# mailboxWiFi.net
KiCad netlist of a schematic drawn in EAGLE
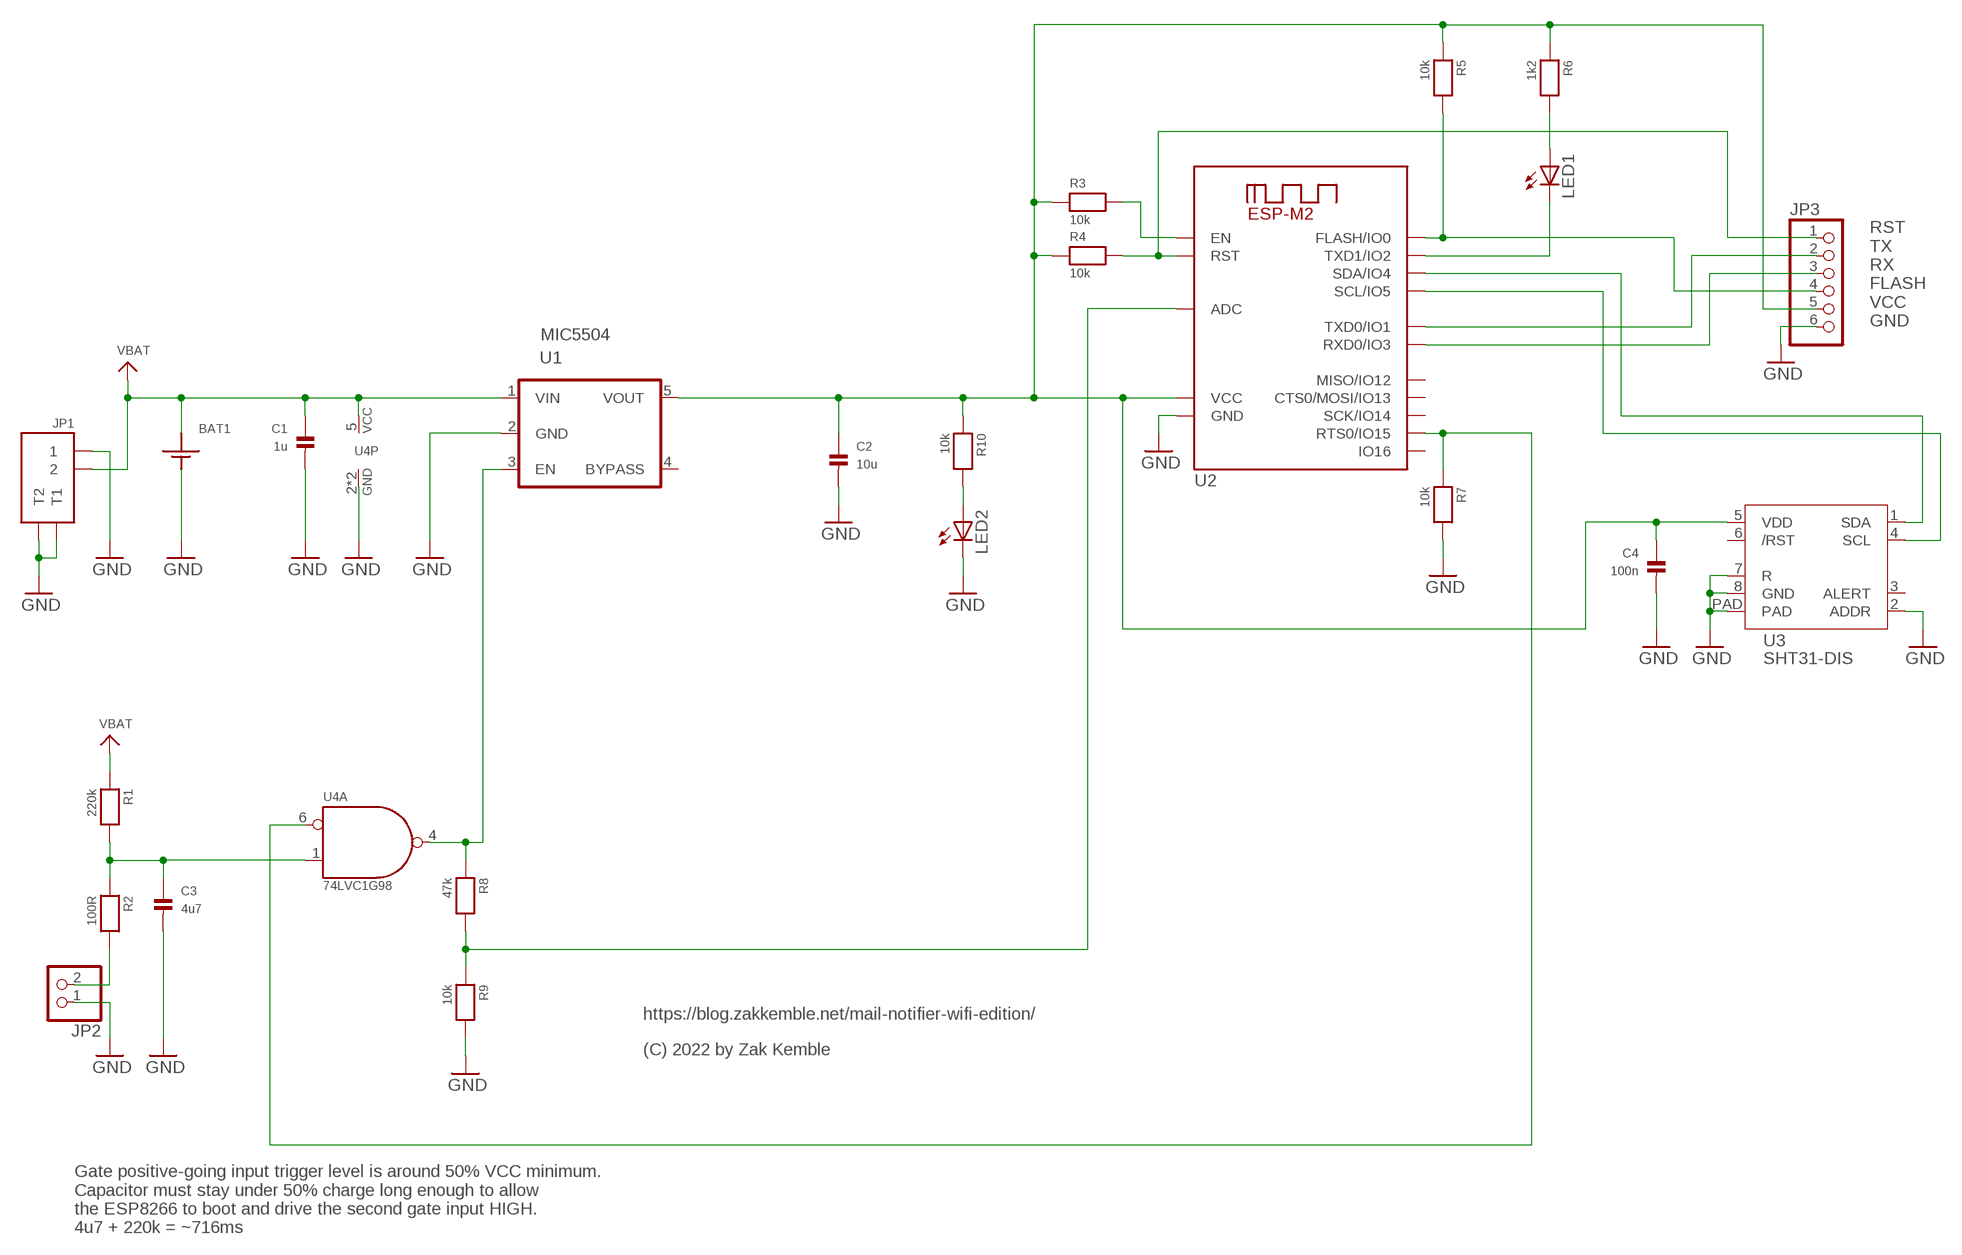
[diagram p0: schematic, sheet 1]

(export (version "E")
  (design (tool "Eeschema 10.0.6"))
  (components
    (comp (ref "BAT1")
      (value "BATTERY_HOLDER1XAAA_PCB")
      (footprint "eagle-import:BATT_HOLDER_AAA_PCB")
      (libsource (lib "eagle-import") (part "BATTERY_HOLDER1XAAA_PCB"))
    )
    (comp (ref "C1")
      (value "1u")
      (footprint "eagle-import:0805_NO_OUTLINE")
      (libsource (lib "eagle-import") (part "CAP_CERAMIC0805"))
    )
    (comp (ref "C2")
      (value "10u")
      (footprint "eagle-import:1206")
      (libsource (lib "eagle-import") (part "CAP_CERAMIC1206"))
    )
    (comp (ref "C3")
      (value "4u7")
      (footprint "eagle-import:0805_NO_OUTLINE")
      (libsource (lib "eagle-import") (part "CAP_CERAMIC0805"))
    )
    (comp (ref "C4")
      (value "100n")
      (footprint "eagle-import:0402_XSMALL")
      (libsource (lib "eagle-import") (part "CAP_CERAMIC0402_XSMALL"))
    )
    (comp (ref "JP1")
      (value "2WAY-SMDVERT")
      (footprint "eagle-import:2WAY-SMD")
      (libsource (lib "eagle-import") (part "2WAY-SMDVERT"))
    )
    (comp (ref "JP2")
      (value "PINHD-1X2/90")
      (footprint "eagle-import:1X02_90")
      (libsource (lib "eagle-import") (part "PINHD-1X2/90"))
    )
    (comp (ref "JP3")
      (value "PINHD-1X6")
      (footprint "eagle-import:1X06")
      (libsource (lib "eagle-import") (part "PINHD-1X6"))
    )
    (comp (ref "LED1")
      (value "LED0402_XSMALL")
      (footprint "eagle-import:0402_DIODE_XSMALL")
      (libsource (lib "eagle-import") (part "LED0402_XSMALL"))
    )
    (comp (ref "LED2")
      (value "LED0402_XSMALL")
      (footprint "eagle-import:0402_DIODE_XSMALL")
      (libsource (lib "eagle-import") (part "LED0402_XSMALL"))
    )
    (comp (ref "R1")
      (value "220k")
      (footprint "eagle-import:0402_XSMALL")
      (libsource (lib "eagle-import") (part "RESISTOR0402_XSMALL"))
    )
    (comp (ref "R2")
      (value "100R")
      (footprint "eagle-import:0402_XSMALL")
      (libsource (lib "eagle-import") (part "RESISTOR0402_XSMALL"))
    )
    (comp (ref "R3")
      (value "10k")
      (footprint "eagle-import:0402_XSMALL")
      (libsource (lib "eagle-import") (part "RESISTOR0402_XSMALL"))
    )
    (comp (ref "R4")
      (value "10k")
      (footprint "eagle-import:0402_XSMALL")
      (libsource (lib "eagle-import") (part "RESISTOR0402_XSMALL"))
    )
    (comp (ref "R5")
      (value "10k")
      (footprint "eagle-import:0402_XSMALL")
      (libsource (lib "eagle-import") (part "RESISTOR0402_XSMALL"))
    )
    (comp (ref "R6")
      (value "1k2")
      (footprint "eagle-import:0402_XSMALL")
      (libsource (lib "eagle-import") (part "RESISTOR0402_XSMALL"))
    )
    (comp (ref "R7")
      (value "10k")
      (footprint "eagle-import:0402_XSMALL")
      (libsource (lib "eagle-import") (part "RESISTOR0402_XSMALL"))
    )
    (comp (ref "R8")
      (value "47k")
      (footprint "eagle-import:0402_XSMALL")
      (libsource (lib "eagle-import") (part "RESISTOR0402_XSMALL"))
    )
    (comp (ref "R9")
      (value "10k")
      (footprint "eagle-import:0402_XSMALL")
      (libsource (lib "eagle-import") (part "RESISTOR0402_XSMALL"))
    )
    (comp (ref "R10")
      (value "10k")
      (footprint "eagle-import:0402_XSMALL")
      (libsource (lib "eagle-import") (part "RESISTOR0402_XSMALL"))
    )
    (comp (ref "U1")
      (value "MIC5504")
      (footprint "eagle-import:SOT23-5_SM_PAD")
      (libsource (lib "eagle-import") (part "REGULATOR_5SOT23-5"))
    )
    (comp (ref "U2")
      (value "ESP-M2")
      (footprint "eagle-import:ESP-M2")
      (libsource (lib "eagle-import") (part "ESP-M2"))
    )
    (comp (ref "U3")
      (value "SHT31-DIS")
      (footprint "eagle-import:DFN_2.5X2.5_8")
      (libsource (lib "eagle-import") (part "SHT3X-DIS"))
    )
    (comp (ref "U4")
      (value "74LVC1G98")
      (footprint "eagle-import:SOT-363")
      (libsource (lib "eagle-import") (part "74LVC1G98-NAND_1INVSOT-363"))
    )
  )
  (nets
    (net (code "1") (name "GND") (class "Default")
      (node (ref "BAT1") (pin "NEG") (pinfunction "NEG_NEG") (pintype "passive"))
      (node (ref "C1") (pin "2") (pinfunction "P$2_2") (pintype "passive"))
      (node (ref "C2") (pin "2") (pinfunction "P$2_2") (pintype "passive"))
      (node (ref "C3") (pin "2") (pinfunction "P$2_2") (pintype "passive"))
      (node (ref "C4") (pin "2") (pinfunction "P$2_2") (pintype "passive"))
      (node (ref "JP1") (pin "1") (pinfunction "1_1") (pintype "passive"))
      (node (ref "JP1") (pin "TAB$1") (pinfunction "T1_TAB$1") (pintype "passive"))
      (node (ref "JP1") (pin "TAB$2") (pinfunction "T2_TAB$2") (pintype "passive"))
      (node (ref "JP2") (pin "1") (pinfunction "1_1") (pintype "passive"))
      (node (ref "JP3") (pin "6") (pinfunction "6_6") (pintype "passive"))
      (node (ref "LED2") (pin "2") (pinfunction "C_2") (pintype "passive"))
      (node (ref "R7") (pin "2") (pinfunction "2_2") (pintype "passive"))
      (node (ref "R9") (pin "2") (pinfunction "2_2") (pintype "passive"))
      (node (ref "U1") (pin "2") (pinfunction "GND_2") (pintype "passive"))
      (node (ref "U2") (pin "8") (pinfunction "GND_8") (pintype "bidirectional"))
      (node (ref "U3") (pin "2") (pinfunction "ADDR_2") (pintype "bidirectional"))
      (node (ref "U3") (pin "7") (pinfunction "R_7") (pintype "bidirectional"))
      (node (ref "U3") (pin "8") (pinfunction "GND_8") (pintype "bidirectional"))
      (node (ref "U3") (pin "PAD") (pinfunction "PAD_PAD") (pintype "bidirectional"))
      (node (ref "U4") (pin "2") (pinfunction "GND_2") (pintype "power_in"))
      (node (ref "U4") (pin "3") (pinfunction "GND_3") (pintype "power_in"))
    )
    (net (code "2") (name "Net-(C2-P$1)") (class "Default")
      (node (ref "C2") (pin "1") (pinfunction "P$1_1") (pintype "passive"))
      (node (ref "C4") (pin "1") (pinfunction "P$1_1") (pintype "passive"))
      (node (ref "JP3") (pin "5") (pinfunction "5_5") (pintype "passive"))
      (node (ref "R10") (pin "1") (pinfunction "1_1") (pintype "passive"))
      (node (ref "R3") (pin "1") (pinfunction "1_1") (pintype "passive"))
      (node (ref "R4") (pin "1") (pinfunction "1_1") (pintype "passive"))
      (node (ref "R5") (pin "1") (pinfunction "1_1") (pintype "passive"))
      (node (ref "R6") (pin "1") (pinfunction "1_1") (pintype "passive"))
      (node (ref "U1") (pin "5") (pinfunction "VOUT_5") (pintype "output"))
      (node (ref "U2") (pin "7") (pinfunction "VCC_7") (pintype "bidirectional"))
      (node (ref "U3") (pin "5") (pinfunction "VDD_5") (pintype "bidirectional"))
    )
    (net (code "3") (name "Net-(C3-P$1)") (class "Default")
      (node (ref "C3") (pin "1") (pinfunction "P$1_1") (pintype "passive"))
      (node (ref "R1") (pin "2") (pinfunction "2_2") (pintype "passive"))
      (node (ref "R2") (pin "1") (pinfunction "1_1") (pintype "passive"))
      (node (ref "U4") (pin "1") (pinfunction "B_1") (pintype "input"))
    )
    (net (code "4") (name "Net-(JP2-Pad2)") (class "Default")
      (node (ref "JP2") (pin "2") (pinfunction "2_2") (pintype "passive"))
      (node (ref "R2") (pin "2") (pinfunction "2_2") (pintype "passive"))
    )
    (net (code "5") (name "Net-(LED1-A)") (class "Default")
      (node (ref "LED1") (pin "1") (pinfunction "A_1") (pintype "passive"))
      (node (ref "R6") (pin "2") (pinfunction "2_2") (pintype "passive"))
    )
    (net (code "6") (name "Net-(LED1-C)") (class "Default")
      (node (ref "LED1") (pin "2") (pinfunction "C_2") (pintype "passive"))
      (node (ref "U2") (pin "9") (pinfunction "TXD1/IO2_9") (pintype "bidirectional"))
    )
    (net (code "7") (name "Net-(LED2-A)") (class "Default")
      (node (ref "LED2") (pin "1") (pinfunction "A_1") (pintype "passive"))
      (node (ref "R10") (pin "2") (pinfunction "2_2") (pintype "passive"))
    )
    (net (code "8") (name "Net-(U1-EN)") (class "Default")
      (node (ref "R8") (pin "1") (pinfunction "1_1") (pintype "passive"))
      (node (ref "U1") (pin "3") (pinfunction "EN_3") (pintype "input"))
      (node (ref "U4") (pin "4") (pinfunction "Y_4") (pintype "output"))
    )
    (net (code "9") (name "Net-(U2-ADC)") (class "Default")
      (node (ref "R8") (pin "2") (pinfunction "2_2") (pintype "passive"))
      (node (ref "R9") (pin "1") (pinfunction "1_1") (pintype "passive"))
      (node (ref "U2") (pin "1") (pinfunction "ADC_1") (pintype "bidirectional"))
    )
    (net (code "10") (name "Net-(U2-EN)") (class "Default")
      (node (ref "R3") (pin "2") (pinfunction "2_2") (pintype "passive"))
      (node (ref "U2") (pin "2") (pinfunction "EN_2") (pintype "bidirectional"))
    )
    (net (code "11") (name "Net-(U2-FLASH{slash}IO0)") (class "Default")
      (node (ref "JP3") (pin "4") (pinfunction "4_4") (pintype "passive"))
      (node (ref "R5") (pin "2") (pinfunction "2_2") (pintype "passive"))
      (node (ref "U2") (pin "10") (pinfunction "FLASH/IO0_10") (pintype "bidirectional"))
    )
    (net (code "12") (name "Net-(U2-RST)") (class "Default")
      (node (ref "JP3") (pin "1") (pinfunction "1_1") (pintype "passive"))
      (node (ref "R4") (pin "2") (pinfunction "2_2") (pintype "passive"))
      (node (ref "U2") (pin "15") (pinfunction "RST_15") (pintype "bidirectional"))
    )
    (net (code "13") (name "Net-(U2-RTS0{slash}IO15)") (class "Default")
      (node (ref "R7") (pin "1") (pinfunction "1_1") (pintype "passive"))
      (node (ref "U2") (pin "6") (pinfunction "RTS0/IO15_6") (pintype "bidirectional"))
      (node (ref "U4") (pin "6") (pinfunction "A_6") (pintype "input"))
    )
    (net (code "14") (name "Net-(U2-RXD0{slash}IO3)") (class "Default")
      (node (ref "JP3") (pin "3") (pinfunction "3_3") (pintype "passive"))
      (node (ref "U2") (pin "13") (pinfunction "RXD0/IO3_13") (pintype "bidirectional"))
    )
    (net (code "15") (name "Net-(U2-SCL{slash}IO5)") (class "Default")
      (node (ref "U2") (pin "12") (pinfunction "SCL/IO5_12") (pintype "bidirectional"))
      (node (ref "U3") (pin "4") (pinfunction "SCL_4") (pintype "bidirectional"))
    )
    (net (code "16") (name "Net-(U2-SDA{slash}IO4)") (class "Default")
      (node (ref "U2") (pin "11") (pinfunction "SDA/IO4_11") (pintype "bidirectional"))
      (node (ref "U3") (pin "1") (pinfunction "SDA_1") (pintype "bidirectional"))
    )
    (net (code "17") (name "Net-(U2-TXD0{slash}IO1)") (class "Default")
      (node (ref "JP3") (pin "2") (pinfunction "2_2") (pintype "passive"))
      (node (ref "U2") (pin "14") (pinfunction "TXD0/IO1_14") (pintype "bidirectional"))
    )
    (net (code "18") (name "VBAT") (class "Default")
      (node (ref "BAT1") (pin "POS") (pinfunction "POS_POS") (pintype "power_in"))
      (node (ref "C1") (pin "1") (pinfunction "P$1_1") (pintype "passive"))
      (node (ref "JP1") (pin "2") (pinfunction "2_2") (pintype "passive"))
      (node (ref "R1") (pin "1") (pinfunction "1_1") (pintype "passive"))
      (node (ref "U1") (pin "1") (pinfunction "VIN_1") (pintype "power_in"))
      (node (ref "U4") (pin "5") (pinfunction "VCC_5") (pintype "power_in"))
    )
    (net (code "19") (name "unconnected-(U1-BYPASS-Pad4)") (class "Default")
      (node (ref "U1") (pin "4") (pinfunction "BYPASS_4") (pintype "passive"))
    )
    (net (code "20") (name "unconnected-(U2-CTS0{slash}MOSI{slash}IO13-Pad5)") (class "Default")
      (node (ref "U2") (pin "5") (pinfunction "CTS0/MOSI/IO13_5") (pintype "bidirectional"))
    )
    (net (code "21") (name "unconnected-(U2-IO16-Pad16)") (class "Default")
      (node (ref "U2") (pin "16") (pinfunction "IO16_16") (pintype "bidirectional"))
    )
    (net (code "22") (name "unconnected-(U2-MISO{slash}IO12-Pad4)") (class "Default")
      (node (ref "U2") (pin "4") (pinfunction "MISO/IO12_4") (pintype "bidirectional"))
    )
    (net (code "23") (name "unconnected-(U2-SCK{slash}IO14-Pad3)") (class "Default")
      (node (ref "U2") (pin "3") (pinfunction "SCK/IO14_3") (pintype "bidirectional"))
    )
    (net (code "24") (name "unconnected-(U3-ALERT-Pad3)") (class "Default")
      (node (ref "U3") (pin "3") (pinfunction "ALERT_3") (pintype "bidirectional"))
    )
    (net (code "25") (name "unconnected-(U3-{slash}RST-Pad6)") (class "Default")
      (node (ref "U3") (pin "6") (pinfunction "/RST_6") (pintype "bidirectional"))
    )
  )
)
